# ai_breakout_ft232rl_panel.net
KiCad netlist of a schematic drawn in EAGLE
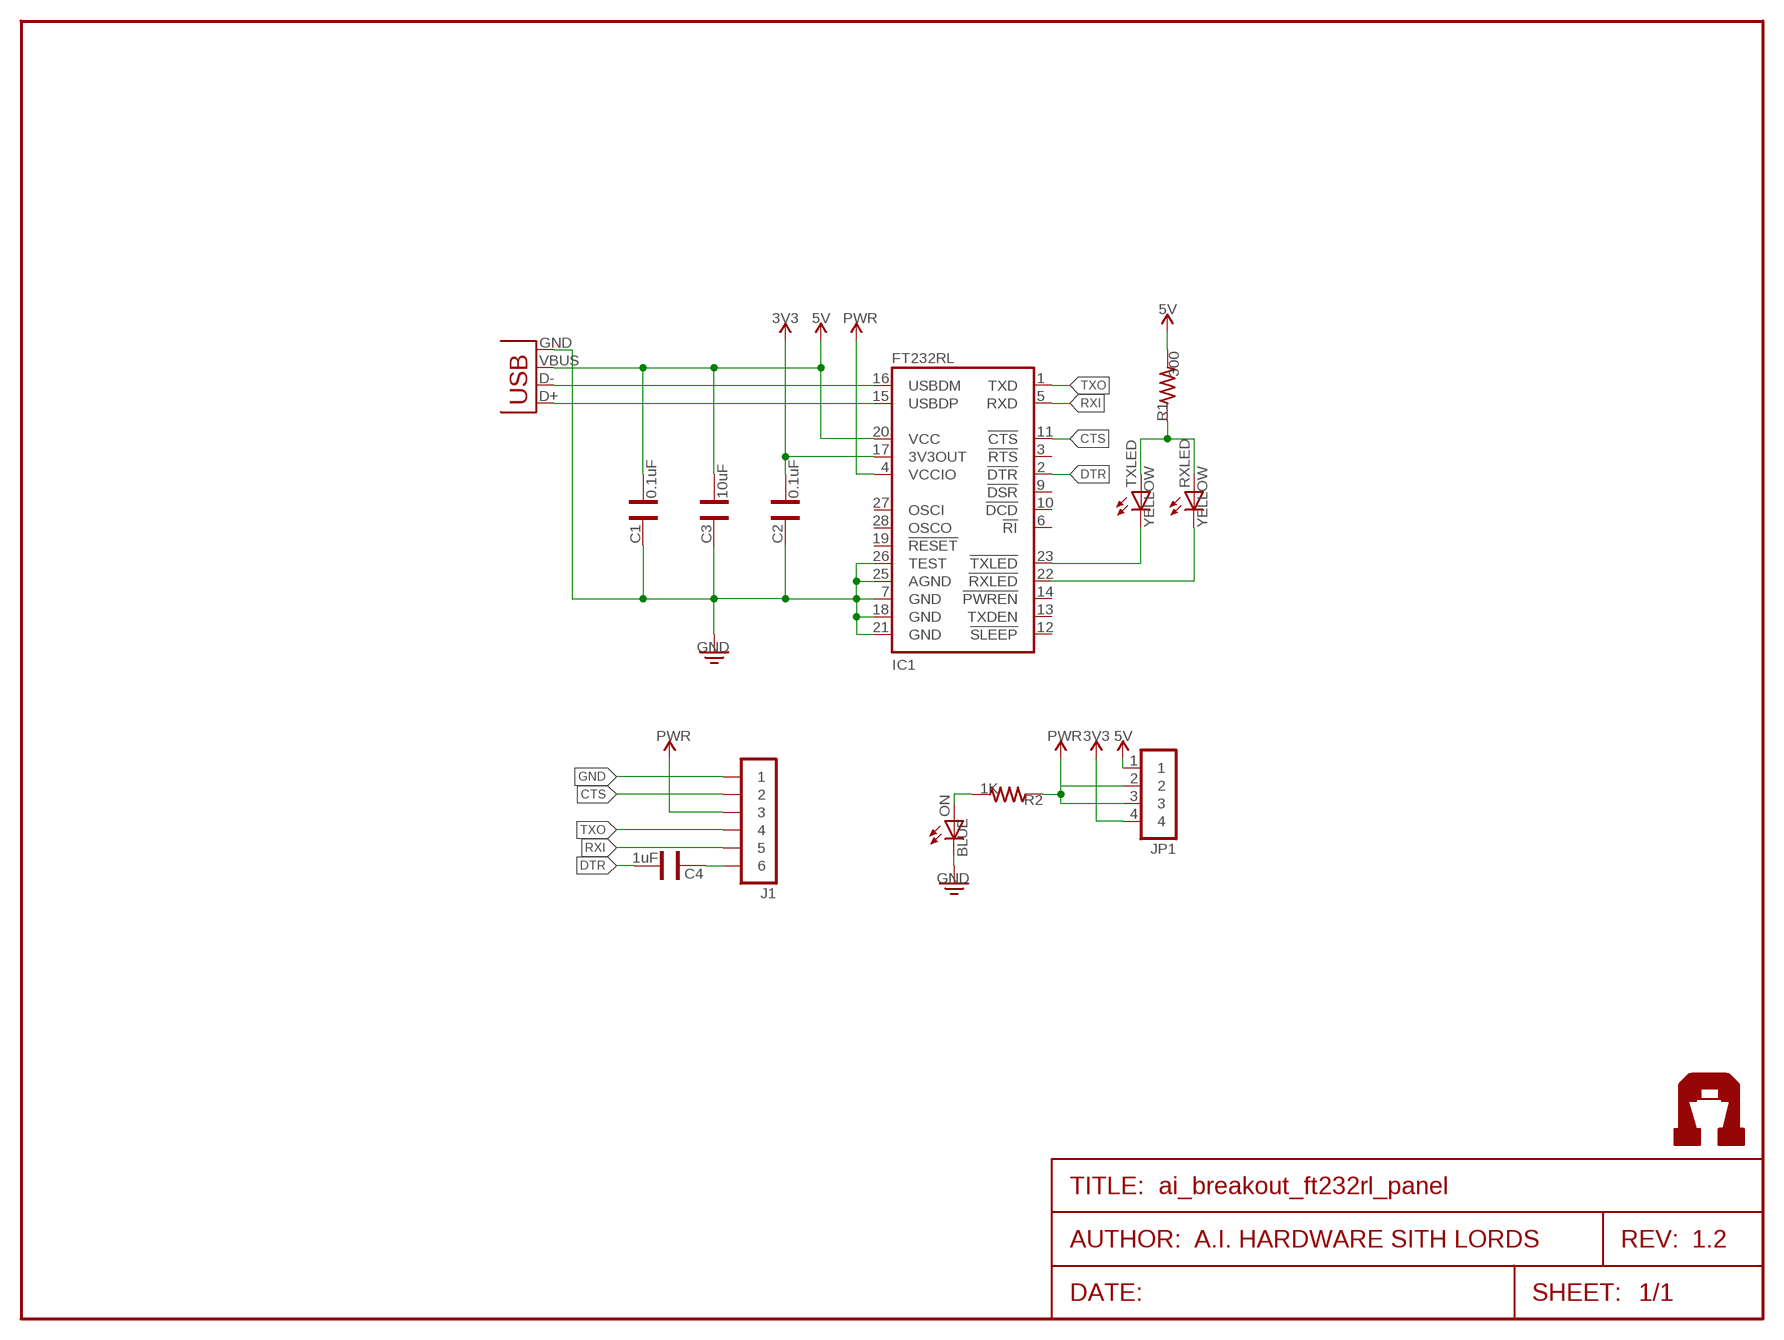
[diagram p0: schematic, sheet 1]

(export (version "E")
  (design (tool "Eeschema 10.0.6"))
  (components
    (comp (ref "C1")
      (value "0.1uF")
      (footprint "eagle-import:CAP-0603")
      (libsource (lib "eagle-import") (part "CAP0603"))
    )
    (comp (ref "C2")
      (value "0.1uF")
      (footprint "eagle-import:CAP-0603")
      (libsource (lib "eagle-import") (part "CAP0603"))
    )
    (comp (ref "C3")
      (value "10uF")
      (footprint "eagle-import:CAP-0603")
      (libsource (lib "eagle-import") (part "CAP0603"))
    )
    (comp (ref "C4")
      (value "1uF")
      (footprint "eagle-import:CAP-0603")
      (libsource (lib "eagle-import") (part "CAP0603"))
    )
    (comp (ref "IC1")
      (value "FT2332RL")
      (footprint "eagle-import:SSOP28-LD")
      (libsource (lib "eagle-import") (part "FT2332RL"))
    )
    (comp (ref "J1")
      (value "1X06LONG")
      (footprint "eagle-import:1X06-LONG")
      (libsource (lib "eagle-import") (part "1X06LONG"))
    )
    (comp (ref "JP1")
      (value "1X04NOSILK")
      (footprint "eagle-import:1X04-NOSILK")
      (libsource (lib "eagle-import") (part "1X04NOSILK"))
    )
    (comp (ref "ON")
      (value "BLUE")
      (footprint "eagle-import:LED-0603")
      (libsource (lib "eagle-import") (part "LED0603"))
    )
    (comp (ref "R1")
      (value "300")
      (footprint "eagle-import:RES-0603")
      (libsource (lib "eagle-import") (part "RES0603"))
    )
    (comp (ref "R2")
      (value "1K")
      (footprint "eagle-import:RES-0603")
      (libsource (lib "eagle-import") (part "RES0603"))
    )
    (comp (ref "RXLED")
      (value "YELLOW")
      (footprint "eagle-import:LED-0603")
      (libsource (lib "eagle-import") (part "LED0603"))
    )
    (comp (ref "TXLED")
      (value "YELLOW")
      (footprint "eagle-import:LED-0603")
      (libsource (lib "eagle-import") (part "LED0603"))
    )
    (comp (ref "U$3")
      (value "AI-LOGOL")
      (footprint "eagle-import:AI-LOGO-L")
      (libsource (lib "eagle-import") (part "AI-LOGOL"))
    )
    (comp (ref "USB1")
      (value "USBMICROB")
      (footprint "eagle-import:USB-MICROB")
      (libsource (lib "eagle-import") (part "USBMICROB"))
    )
  )
  (nets
    (net (code "1") (name "3V3") (class "Default")
      (node (ref "C2") (pin "1") (pinfunction "1_1") (pintype "passive"))
      (node (ref "IC1") (pin "17") (pinfunction "3V3OUT_17") (pintype "power_in"))
      (node (ref "JP1") (pin "4") (pinfunction "4_4") (pintype "bidirectional"))
    )
    (net (code "2") (name "5V") (class "Default")
      (node (ref "C1") (pin "1") (pinfunction "1_1") (pintype "passive"))
      (node (ref "C3") (pin "1") (pinfunction "1_1") (pintype "passive"))
      (node (ref "IC1") (pin "20") (pinfunction "VCC_20") (pintype "power_in"))
      (node (ref "JP1") (pin "1") (pinfunction "1_1") (pintype "bidirectional"))
      (node (ref "R1") (pin "2") (pinfunction "2_2") (pintype "passive"))
      (node (ref "USB1") (pin "VBUS") (pinfunction "VBUS_VBUS") (pintype "bidirectional"))
    )
    (net (code "3") (name "CTS") (class "Default")
      (node (ref "IC1") (pin "11") (pinfunction "~{CTS}_11") (pintype "input"))
      (node (ref "J1") (pin "2") (pinfunction "2_2") (pintype "bidirectional"))
    )
    (net (code "4") (name "DTR") (class "Default")
      (node (ref "C4") (pin "1") (pinfunction "1_1") (pintype "passive"))
      (node (ref "IC1") (pin "2") (pinfunction "~{DTR}_2") (pintype "output"))
    )
    (net (code "5") (name "GND") (class "Default")
      (node (ref "C1") (pin "2") (pinfunction "2_2") (pintype "passive"))
      (node (ref "C2") (pin "2") (pinfunction "2_2") (pintype "passive"))
      (node (ref "C3") (pin "2") (pinfunction "2_2") (pintype "passive"))
      (node (ref "IC1") (pin "18") (pinfunction "GND_18") (pintype "power_in"))
      (node (ref "IC1") (pin "21") (pinfunction "GND_21") (pintype "power_in"))
      (node (ref "IC1") (pin "25") (pinfunction "AGND_25") (pintype "power_in"))
      (node (ref "IC1") (pin "26") (pinfunction "TEST_26") (pintype "input"))
      (node (ref "IC1") (pin "7") (pinfunction "GND_7") (pintype "power_in"))
      (node (ref "J1") (pin "1") (pinfunction "1_1") (pintype "bidirectional"))
      (node (ref "ON") (pin "C") (pinfunction "C_C") (pintype "passive"))
      (node (ref "USB1") (pin "GND") (pinfunction "GND_GND") (pintype "bidirectional"))
    )
    (net (code "6") (name "Net-(C4-Pad2)") (class "Default")
      (node (ref "C4") (pin "2") (pinfunction "2_2") (pintype "passive"))
      (node (ref "J1") (pin "6") (pinfunction "6_6") (pintype "bidirectional"))
    )
    (net (code "7") (name "Net-(IC1-USBDM)") (class "Default")
      (node (ref "IC1") (pin "16") (pinfunction "USBDM_16") (pintype "bidirectional"))
      (node (ref "USB1") (pin "D-") (pinfunction "D-_D-") (pintype "bidirectional"))
    )
    (net (code "8") (name "Net-(IC1-USBDP)") (class "Default")
      (node (ref "IC1") (pin "15") (pinfunction "USBDP_15") (pintype "bidirectional"))
      (node (ref "USB1") (pin "D+") (pinfunction "D+_D+") (pintype "bidirectional"))
    )
    (net (code "9") (name "Net-(IC1-~{RXLED})") (class "Default")
      (node (ref "IC1") (pin "22") (pinfunction "~{RXLED}_22") (pintype "input"))
      (node (ref "RXLED") (pin "C") (pinfunction "C_C") (pintype "passive"))
    )
    (net (code "10") (name "Net-(IC1-~{TXLED})") (class "Default")
      (node (ref "IC1") (pin "23") (pinfunction "~{TXLED}_23") (pintype "input"))
      (node (ref "TXLED") (pin "C") (pinfunction "C_C") (pintype "passive"))
    )
    (net (code "11") (name "Net-(ON-PadA)") (class "Default")
      (node (ref "ON") (pin "A") (pinfunction "A_A") (pintype "passive"))
      (node (ref "R2") (pin "2") (pinfunction "2_2") (pintype "passive"))
    )
    (net (code "12") (name "Net-(R1-Pad1)") (class "Default")
      (node (ref "R1") (pin "1") (pinfunction "1_1") (pintype "passive"))
      (node (ref "RXLED") (pin "A") (pinfunction "A_A") (pintype "passive"))
      (node (ref "TXLED") (pin "A") (pinfunction "A_A") (pintype "passive"))
    )
    (net (code "13") (name "PWR") (class "Default")
      (node (ref "IC1") (pin "4") (pinfunction "VCCIO_4") (pintype "power_in"))
      (node (ref "J1") (pin "3") (pinfunction "3_3") (pintype "bidirectional"))
      (node (ref "JP1") (pin "2") (pinfunction "2_2") (pintype "bidirectional"))
      (node (ref "JP1") (pin "3") (pinfunction "3_3") (pintype "bidirectional"))
      (node (ref "R2") (pin "1") (pinfunction "1_1") (pintype "passive"))
    )
    (net (code "14") (name "RXI") (class "Default")
      (node (ref "IC1") (pin "5") (pinfunction "RXD_5") (pintype "input"))
      (node (ref "J1") (pin "5") (pinfunction "5_5") (pintype "bidirectional"))
    )
    (net (code "15") (name "TXO") (class "Default")
      (node (ref "IC1") (pin "1") (pinfunction "TXD_1") (pintype "output"))
      (node (ref "J1") (pin "4") (pinfunction "4_4") (pintype "bidirectional"))
    )
    (net (code "16") (name "unconnected-(IC1-OSCI-Pad27)") (class "Default")
      (node (ref "IC1") (pin "27") (pinfunction "OSCI_27") (pintype "no_connect"))
    )
    (net (code "17") (name "unconnected-(IC1-OSCO-Pad28)") (class "Default")
      (node (ref "IC1") (pin "28") (pinfunction "OSCO_28") (pintype "output"))
    )
    (net (code "18") (name "unconnected-(IC1-TXDEN-Pad13)") (class "Default")
      (node (ref "IC1") (pin "13") (pinfunction "TXDEN_13") (pintype "no_connect"))
    )
    (net (code "19") (name "unconnected-(IC1-~{DCD}-Pad10)") (class "Default")
      (node (ref "IC1") (pin "10") (pinfunction "~{DCD}_10") (pintype "no_connect"))
    )
    (net (code "20") (name "unconnected-(IC1-~{DSR}-Pad9)") (class "Default")
      (node (ref "IC1") (pin "9") (pinfunction "~{DSR}_9") (pintype "no_connect"))
    )
    (net (code "21") (name "unconnected-(IC1-~{PWREN}-Pad14)") (class "Default")
      (node (ref "IC1") (pin "14") (pinfunction "~{PWREN}_14") (pintype "no_connect"))
    )
    (net (code "22") (name "unconnected-(IC1-~{RESET}-Pad19)") (class "Default")
      (node (ref "IC1") (pin "19") (pinfunction "~{RESET}_19") (pintype "no_connect"))
    )
    (net (code "23") (name "unconnected-(IC1-~{RI}-Pad6)") (class "Default")
      (node (ref "IC1") (pin "6") (pinfunction "~{RI}_6") (pintype "no_connect"))
    )
    (net (code "24") (name "unconnected-(IC1-~{RTS}-Pad3)") (class "Default")
      (node (ref "IC1") (pin "3") (pinfunction "~{RTS}_3") (pintype "output"))
    )
    (net (code "25") (name "unconnected-(IC1-~{SLEEP}-Pad12)") (class "Default")
      (node (ref "IC1") (pin "12") (pinfunction "~{SLEEP}_12") (pintype "no_connect"))
    )
  )
)
